# ELVIS.net
KiCad netlist of a schematic drawn in Altium Designer
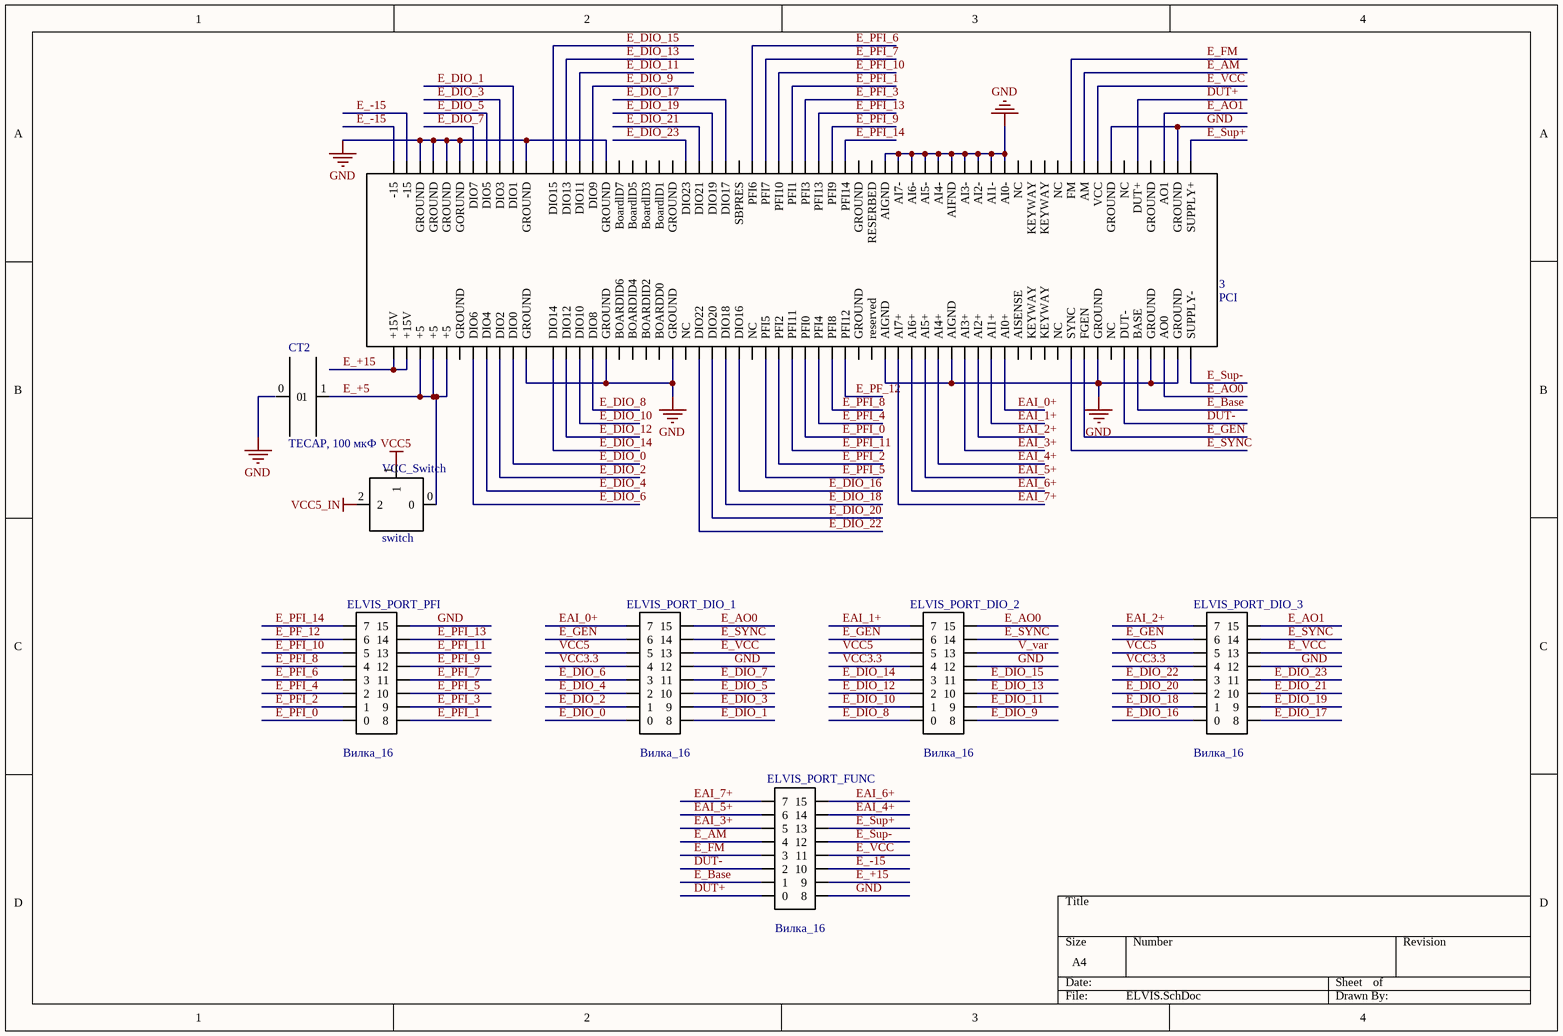
[diagram p0: ELVIS.SchDoc]

(export (version "E")
  (design (tool "Eeschema 10.0.6"))
  (components
    (comp (ref "3") (value "PCI") (footprint "PcbLib1:PCI-120") (libsource (lib "Library") (part "PCI")))
    (comp (ref "CT2")
      (value "TECAP, 100 мкФ")
      (footprint "PcbLib1:tantal cap")
      (libsource (lib "Library") (part "TECAP, 100 мкФ"))
    )
    (comp (ref "ELVIS_PORT_DIO_1")
      (value "Вилка_16")
      (footprint "DS1013-16")
      (description "16_pin")
      (libsource (lib "Library") (part "DS1013-16"))
    )
    (comp (ref "ELVIS_PORT_DIO_2")
      (value "Вилка_16")
      (footprint "DS1013-16")
      (description "16_pin")
      (libsource (lib "Library") (part "DS1013-16"))
    )
    (comp (ref "ELVIS_PORT_DIO_3")
      (value "Вилка_16")
      (footprint "DS1013-16")
      (description "16_pin")
      (libsource (lib "Library") (part "DS1013-16"))
    )
    (comp (ref "ELVIS_PORT_FUNC")
      (value "Вилка_16")
      (footprint "DS1013-16")
      (description "16_pin")
      (libsource (lib "Library") (part "DS1013-16"))
    )
    (comp (ref "ELVIS_PORT_PFI")
      (value "Вилка_16")
      (footprint "DS1013-16")
      (description "16_pin")
      (libsource (lib "Library") (part "DS1013-16"))
    )
    (comp (ref "VCC_Switch")
      (value "switch")
      (footprint "PcbLib1:К(Р)142ЕН5В")
      (libsource (lib "Library") (part "switch"))
    )
  )
  (nets
    (net (code "1") (name "/DUT+") (class "Default")
      (node (ref "3") (pin "63") (pinfunction "DUT+_63") (pintype "passive"))
      (node (ref "ELVIS_PORT_FUNC") (pin "0") (pinfunction "0_0") (pintype "passive"))
    )
    (net (code "2") (name "/DUT-") (class "Default")
      (node (ref "3") (pin "53") (pinfunction "DUT-_53") (pintype "passive"))
      (node (ref "ELVIS_PORT_FUNC") (pin "2") (pinfunction "2_2") (pintype "passive"))
    )
    (net (code "3") (name "/EAI_0+") (class "Default")
      (node (ref "3") (pin "45") (pinfunction "AI0+_45") (pintype "passive"))
      (node (ref "ELVIS_PORT_DIO_1") (pin "7") (pinfunction "7_7") (pintype "passive"))
    )
    (net (code "4") (name "/EAI_1+") (class "Default")
      (node (ref "3") (pin "44") (pinfunction "AI1+_44") (pintype "passive"))
      (node (ref "ELVIS_PORT_DIO_2") (pin "7") (pinfunction "7_7") (pintype "passive"))
    )
    (net (code "5") (name "/EAI_2+") (class "Default")
      (node (ref "3") (pin "43") (pinfunction "AI2+_43") (pintype "passive"))
      (node (ref "ELVIS_PORT_DIO_3") (pin "7") (pinfunction "7_7") (pintype "passive"))
    )
    (net (code "6") (name "/EAI_3+") (class "Default")
      (node (ref "3") (pin "42") (pinfunction "AI3+_42") (pintype "passive"))
      (node (ref "ELVIS_PORT_FUNC") (pin "5") (pinfunction "5_5") (pintype "passive"))
    )
    (net (code "7") (name "/EAI_4+") (class "Default")
      (node (ref "3") (pin "40") (pinfunction "AI4+_40") (pintype "passive"))
      (node (ref "ELVIS_PORT_FUNC") (pin "14") (pinfunction "14_14") (pintype "passive"))
    )
    (net (code "8") (name "/EAI_5+") (class "Default")
      (node (ref "3") (pin "39") (pinfunction "AI5+_39") (pintype "passive"))
      (node (ref "ELVIS_PORT_FUNC") (pin "6") (pinfunction "6_6") (pintype "passive"))
    )
    (net (code "9") (name "/EAI_6+") (class "Default")
      (node (ref "3") (pin "38") (pinfunction "AI6+_38") (pintype "passive"))
      (node (ref "ELVIS_PORT_FUNC") (pin "15") (pinfunction "15_15") (pintype "passive"))
    )
    (net (code "10") (name "/EAI_7+") (class "Default")
      (node (ref "3") (pin "37") (pinfunction "AI7+_37") (pintype "passive"))
      (node (ref "ELVIS_PORT_FUNC") (pin "7") (pinfunction "7_7") (pintype "passive"))
    )
    (net (code "11") (name "/E_+5") (class "Default")
      (node (ref "3") (pin "2") (pinfunction "+5_2") (pintype "passive"))
      (node (ref "3") (pin "3") (pinfunction "+5_3") (pintype "passive"))
      (node (ref "3") (pin "4") (pinfunction "+5_4") (pintype "passive"))
      (node (ref "CT2") (pin "1") (pinfunction "1_1") (pintype "passive"))
      (node (ref "VCC_Switch") (pin "0") (pinfunction "0_0") (pintype "passive"))
    )
    (net (code "12") (name "/E_+15") (class "Default")
      (node (ref "3") (pin "0") (pinfunction "+15V_0") (pintype "passive"))
      (node (ref "3") (pin "1") (pinfunction "+15V_1") (pintype "passive"))
      (node (ref "ELVIS_PORT_FUNC") (pin "9") (pinfunction "9_9") (pintype "passive"))
    )
    (net (code "13") (name "/E_-15") (class "Default")
      (node (ref "3") (pin "116") (pinfunction "-15_116") (pintype "passive"))
      (node (ref "3") (pin "117") (pinfunction "-15_117") (pintype "passive"))
      (node (ref "ELVIS_PORT_FUNC") (pin "10") (pinfunction "10_10") (pintype "passive"))
    )
    (net (code "14") (name "/E_AM") (class "Default")
      (node (ref "3") (pin "67") (pinfunction "AM_67") (pintype "passive"))
      (node (ref "ELVIS_PORT_FUNC") (pin "4") (pinfunction "4_4") (pintype "passive"))
    )
    (net (code "15") (name "/E_AO0") (class "Default")
      (node (ref "3") (pin "56") (pinfunction "AO0_56") (pintype "passive"))
      (node (ref "ELVIS_PORT_DIO_1") (pin "15") (pinfunction "15_15") (pintype "passive"))
      (node (ref "ELVIS_PORT_DIO_2") (pin "15") (pinfunction "15_15") (pintype "passive"))
    )
    (net (code "16") (name "/E_AO1") (class "Default")
      (node (ref "3") (pin "61") (pinfunction "AO1_61") (pintype "passive"))
      (node (ref "ELVIS_PORT_DIO_3") (pin "15") (pinfunction "15_15") (pintype "passive"))
    )
    (net (code "17") (name "/E_Base") (class "Default")
      (node (ref "3") (pin "54") (pinfunction "BASE_54") (pintype "passive"))
      (node (ref "ELVIS_PORT_FUNC") (pin "1") (pinfunction "1_1") (pintype "passive"))
    )
    (net (code "18") (name "/E_DIO_0") (class "Default")
      (node (ref "3") (pin "9") (pinfunction "DIO0_9") (pintype "passive"))
      (node (ref "ELVIS_PORT_DIO_1") (pin "0") (pinfunction "0_0") (pintype "passive"))
    )
    (net (code "19") (name "/E_DIO_1") (class "Default")
      (node (ref "3") (pin "108") (pinfunction "DIO1_108") (pintype "passive"))
      (node (ref "ELVIS_PORT_DIO_1") (pin "8") (pinfunction "8_8") (pintype "passive"))
    )
    (net (code "20") (name "/E_DIO_2") (class "Default")
      (node (ref "3") (pin "8") (pinfunction "DIO2_8") (pintype "passive"))
      (node (ref "ELVIS_PORT_DIO_1") (pin "1") (pinfunction "1_1") (pintype "passive"))
    )
    (net (code "21") (name "/E_DIO_3") (class "Default")
      (node (ref "3") (pin "109") (pinfunction "DIO3_109") (pintype "passive"))
      (node (ref "ELVIS_PORT_DIO_1") (pin "9") (pinfunction "9_9") (pintype "passive"))
    )
    (net (code "22") (name "/E_DIO_4") (class "Default")
      (node (ref "3") (pin "7") (pinfunction "DIO4_7") (pintype "passive"))
      (node (ref "ELVIS_PORT_DIO_1") (pin "2") (pinfunction "2_2") (pintype "passive"))
    )
    (net (code "23") (name "/E_DIO_5") (class "Default")
      (node (ref "3") (pin "110") (pinfunction "DIO5_110") (pintype "passive"))
      (node (ref "ELVIS_PORT_DIO_1") (pin "10") (pinfunction "10_10") (pintype "passive"))
    )
    (net (code "24") (name "/E_DIO_6") (class "Default")
      (node (ref "3") (pin "6") (pinfunction "DIO6_6") (pintype "passive"))
      (node (ref "ELVIS_PORT_DIO_1") (pin "3") (pinfunction "3_3") (pintype "passive"))
    )
    (net (code "25") (name "/E_DIO_7") (class "Default")
      (node (ref "3") (pin "111") (pinfunction "DIO7_111") (pintype "passive"))
      (node (ref "ELVIS_PORT_DIO_1") (pin "11") (pinfunction "11_11") (pintype "passive"))
    )
    (net (code "26") (name "/E_DIO_8") (class "Default")
      (node (ref "3") (pin "14") (pinfunction "DIO8_14") (pintype "passive"))
      (node (ref "ELVIS_PORT_DIO_2") (pin "0") (pinfunction "0_0") (pintype "passive"))
    )
    (net (code "27") (name "/E_DIO_9") (class "Default")
      (node (ref "3") (pin "103") (pinfunction "DIO9_103") (pintype "passive"))
      (node (ref "ELVIS_PORT_DIO_2") (pin "8") (pinfunction "8_8") (pintype "passive"))
    )
    (net (code "28") (name "/E_DIO_10") (class "Default")
      (node (ref "3") (pin "13") (pinfunction "DIO10_13") (pintype "passive"))
      (node (ref "ELVIS_PORT_DIO_2") (pin "1") (pinfunction "1_1") (pintype "passive"))
    )
    (net (code "29") (name "/E_DIO_11") (class "Default")
      (node (ref "3") (pin "104") (pinfunction "DIO11_104") (pintype "passive"))
      (node (ref "ELVIS_PORT_DIO_2") (pin "9") (pinfunction "9_9") (pintype "passive"))
    )
    (net (code "30") (name "/E_DIO_12") (class "Default")
      (node (ref "3") (pin "12") (pinfunction "DIO12_12") (pintype "passive"))
      (node (ref "ELVIS_PORT_DIO_2") (pin "2") (pinfunction "2_2") (pintype "passive"))
    )
    (net (code "31") (name "/E_DIO_13") (class "Default")
      (node (ref "3") (pin "105") (pinfunction "DIO13_105") (pintype "passive"))
      (node (ref "ELVIS_PORT_DIO_2") (pin "10") (pinfunction "10_10") (pintype "passive"))
    )
    (net (code "32") (name "/E_DIO_14") (class "Default")
      (node (ref "3") (pin "11") (pinfunction "DIO14_11") (pintype "passive"))
      (node (ref "ELVIS_PORT_DIO_2") (pin "3") (pinfunction "3_3") (pintype "passive"))
    )
    (net (code "33") (name "/E_DIO_15") (class "Default")
      (node (ref "3") (pin "106") (pinfunction "DIO15_106") (pintype "passive"))
      (node (ref "ELVIS_PORT_DIO_2") (pin "11") (pinfunction "11_11") (pintype "passive"))
    )
    (net (code "34") (name "/E_DIO_16") (class "Default")
      (node (ref "3") (pin "25") (pinfunction "DIO16_25") (pintype "passive"))
      (node (ref "ELVIS_PORT_DIO_3") (pin "0") (pinfunction "0_0") (pintype "passive"))
    )
    (net (code "35") (name "/E_DIO_17") (class "Default")
      (node (ref "3") (pin "93") (pinfunction "DIO17_93") (pintype "passive"))
      (node (ref "ELVIS_PORT_DIO_3") (pin "8") (pinfunction "8_8") (pintype "passive"))
    )
    (net (code "36") (name "/E_DIO_18") (class "Default")
      (node (ref "3") (pin "24") (pinfunction "DIO18_24") (pintype "passive"))
      (node (ref "ELVIS_PORT_DIO_3") (pin "1") (pinfunction "1_1") (pintype "passive"))
    )
    (net (code "37") (name "/E_DIO_19") (class "Default")
      (node (ref "3") (pin "94") (pinfunction "DIO19_94") (pintype "passive"))
      (node (ref "ELVIS_PORT_DIO_3") (pin "9") (pinfunction "9_9") (pintype "passive"))
    )
    (net (code "38") (name "/E_DIO_20") (class "Default")
      (node (ref "3") (pin "23") (pinfunction "DIO20_23") (pintype "passive"))
      (node (ref "ELVIS_PORT_DIO_3") (pin "2") (pinfunction "2_2") (pintype "passive"))
    )
    (net (code "39") (name "/E_DIO_21") (class "Default")
      (node (ref "3") (pin "95") (pinfunction "DIO21_95") (pintype "passive"))
      (node (ref "ELVIS_PORT_DIO_3") (pin "10") (pinfunction "10_10") (pintype "passive"))
    )
    (net (code "40") (name "/E_DIO_22") (class "Default")
      (node (ref "3") (pin "22") (pinfunction "DIO22_22") (pintype "passive"))
      (node (ref "ELVIS_PORT_DIO_3") (pin "3") (pinfunction "3_3") (pintype "passive"))
    )
    (net (code "41") (name "/E_DIO_23") (class "Default")
      (node (ref "3") (pin "96") (pinfunction "DIO23_96") (pintype "passive"))
      (node (ref "ELVIS_PORT_DIO_3") (pin "11") (pinfunction "11_11") (pintype "passive"))
    )
    (net (code "42") (name "/E_FM") (class "Default")
      (node (ref "3") (pin "68") (pinfunction "FM_68") (pintype "passive"))
      (node (ref "ELVIS_PORT_FUNC") (pin "3") (pinfunction "3_3") (pintype "passive"))
    )
    (net (code "43") (name "/E_GEN") (class "Default")
      (node (ref "3") (pin "50") (pinfunction "FGEN_50") (pintype "passive"))
      (node (ref "ELVIS_PORT_DIO_1") (pin "6") (pinfunction "6_6") (pintype "passive"))
      (node (ref "ELVIS_PORT_DIO_2") (pin "6") (pinfunction "6_6") (pintype "passive"))
      (node (ref "ELVIS_PORT_DIO_3") (pin "6") (pinfunction "6_6") (pintype "passive"))
    )
    (net (code "44") (name "/E_PFI_0") (class "Default")
      (node (ref "3") (pin "30") (pinfunction "PFI0_30") (pintype "passive"))
      (node (ref "ELVIS_PORT_PFI") (pin "0") (pinfunction "0_0") (pintype "passive"))
    )
    (net (code "45") (name "/E_PFI_1") (class "Default")
      (node (ref "3") (pin "88") (pinfunction "PFI1_88") (pintype "passive"))
      (node (ref "ELVIS_PORT_PFI") (pin "8") (pinfunction "8_8") (pintype "passive"))
    )
    (net (code "46") (name "/E_PFI_2") (class "Default")
      (node (ref "3") (pin "28") (pinfunction "PFI2_28") (pintype "passive"))
      (node (ref "ELVIS_PORT_PFI") (pin "1") (pinfunction "1_1") (pintype "passive"))
    )
    (net (code "47") (name "/E_PFI_3") (class "Default")
      (node (ref "3") (pin "87") (pinfunction "PFI3_87") (pintype "passive"))
      (node (ref "ELVIS_PORT_PFI") (pin "9") (pinfunction "9_9") (pintype "passive"))
    )
    (net (code "48") (name "/E_PFI_4") (class "Default")
      (node (ref "3") (pin "31") (pinfunction "PFI4_31") (pintype "passive"))
      (node (ref "ELVIS_PORT_PFI") (pin "2") (pinfunction "2_2") (pintype "passive"))
    )
    (net (code "49") (name "/E_PFI_5") (class "Default")
      (node (ref "3") (pin "27") (pinfunction "PFI5_27") (pintype "passive"))
      (node (ref "ELVIS_PORT_PFI") (pin "10") (pinfunction "10_10") (pintype "passive"))
    )
    (net (code "50") (name "/E_PFI_6") (class "Default")
      (node (ref "3") (pin "91") (pinfunction "PFI6_91") (pintype "passive"))
      (node (ref "ELVIS_PORT_PFI") (pin "3") (pinfunction "3_3") (pintype "passive"))
    )
    (net (code "51") (name "/E_PFI_7") (class "Default")
      (node (ref "3") (pin "90") (pinfunction "PFI7_90") (pintype "passive"))
      (node (ref "ELVIS_PORT_PFI") (pin "11") (pinfunction "11_11") (pintype "passive"))
    )
    (net (code "52") (name "/E_PFI_8") (class "Default")
      (node (ref "3") (pin "32") (pinfunction "PFI8_32") (pintype "passive"))
      (node (ref "ELVIS_PORT_PFI") (pin "4") (pinfunction "4_4") (pintype "passive"))
    )
    (net (code "53") (name "/E_PFI_9") (class "Default")
      (node (ref "3") (pin "85") (pinfunction "PFI9_85") (pintype "passive"))
      (node (ref "ELVIS_PORT_PFI") (pin "12") (pinfunction "12_12") (pintype "passive"))
    )
    (net (code "54") (name "/E_PFI_10") (class "Default")
      (node (ref "3") (pin "89") (pinfunction "PFI10_89") (pintype "passive"))
      (node (ref "ELVIS_PORT_PFI") (pin "5") (pinfunction "5_5") (pintype "passive"))
    )
    (net (code "55") (name "/E_PFI_11") (class "Default")
      (node (ref "3") (pin "29") (pinfunction "PFI11_29") (pintype "passive"))
      (node (ref "ELVIS_PORT_PFI") (pin "13") (pinfunction "13_13") (pintype "passive"))
    )
    (net (code "56") (name "/E_PFI_13") (class "Default")
      (node (ref "3") (pin "86") (pinfunction "PFI13_86") (pintype "passive"))
      (node (ref "ELVIS_PORT_PFI") (pin "14") (pinfunction "14_14") (pintype "passive"))
    )
    (net (code "57") (name "/E_PFI_14") (class "Default")
      (node (ref "3") (pin "84") (pinfunction "PFI14_84") (pintype "passive"))
      (node (ref "ELVIS_PORT_PFI") (pin "7") (pinfunction "7_7") (pintype "passive"))
    )
    (net (code "58") (name "/E_PF_12") (class "Default")
      (node (ref "3") (pin "33") (pinfunction "PFI12_33") (pintype "passive"))
      (node (ref "ELVIS_PORT_PFI") (pin "6") (pinfunction "6_6") (pintype "passive"))
    )
    (net (code "59") (name "/E_SYNC") (class "Default")
      (node (ref "3") (pin "49") (pinfunction "SYNC_49") (pintype "passive"))
      (node (ref "ELVIS_PORT_DIO_1") (pin "14") (pinfunction "14_14") (pintype "passive"))
      (node (ref "ELVIS_PORT_DIO_2") (pin "14") (pinfunction "14_14") (pintype "passive"))
      (node (ref "ELVIS_PORT_DIO_3") (pin "14") (pinfunction "14_14") (pintype "passive"))
    )
    (net (code "60") (name "/E_Sup+") (class "Default")
      (node (ref "3") (pin "59") (pinfunction "SUPPLY+_59") (pintype "passive"))
      (node (ref "ELVIS_PORT_FUNC") (pin "13") (pinfunction "13_13") (pintype "passive"))
    )
    (net (code "61") (name "/E_Sup-") (class "Default")
      (node (ref "3") (pin "58") (pinfunction "SUPPLY-_58") (pintype "passive"))
      (node (ref "ELVIS_PORT_FUNC") (pin "12") (pinfunction "12_12") (pintype "passive"))
    )
    (net (code "62") (name "/E_VCC") (class "Default")
      (node (ref "3") (pin "66") (pinfunction "VCC_66") (pintype "passive"))
      (node (ref "ELVIS_PORT_DIO_1") (pin "13") (pinfunction "13_13") (pintype "passive"))
      (node (ref "ELVIS_PORT_DIO_3") (pin "13") (pinfunction "13_13") (pintype "passive"))
      (node (ref "ELVIS_PORT_FUNC") (pin "11") (pinfunction "11_11") (pintype "passive"))
    )
    (net (code "63") (name "/VCC3.3") (class "Default")
      (node (ref "ELVIS_PORT_DIO_1") (pin "4") (pinfunction "4_4") (pintype "passive"))
      (node (ref "ELVIS_PORT_DIO_2") (pin "4") (pinfunction "4_4") (pintype "passive"))
      (node (ref "ELVIS_PORT_DIO_3") (pin "4") (pinfunction "4_4") (pintype "passive"))
    )
    (net (code "64") (name "/V_var") (class "Default")
      (node (ref "ELVIS_PORT_DIO_2") (pin "13") (pinfunction "13_13") (pintype "passive"))
    )
    (net (code "65") (name "GND") (class "Default")
      (node (ref "3") (pin "10") (pinfunction "GROUND_10") (pintype "passive"))
      (node (ref "3") (pin "102") (pinfunction "GROUND_102") (pintype "passive"))
      (node (ref "3") (pin "107") (pinfunction "GROUND_107") (pintype "passive"))
      (node (ref "3") (pin "112") (pinfunction "GORUND_112") (pintype "passive"))
      (node (ref "3") (pin "113") (pinfunction "GROUND_113") (pintype "passive"))
      (node (ref "3") (pin "114") (pinfunction "GROUND_114") (pintype "passive"))
      (node (ref "3") (pin "115") (pinfunction "GROUND_115") (pintype "passive"))
      (node (ref "3") (pin "15") (pinfunction "GROUND_15") (pintype "passive"))
      (node (ref "3") (pin "20") (pinfunction "GROUND_20") (pintype "passive"))
      (node (ref "3") (pin "36") (pinfunction "AIGND_36") (pintype "passive"))
      (node (ref "3") (pin "41") (pinfunction "AIGND_41") (pintype "passive"))
      (node (ref "3") (pin "51") (pinfunction "GROUND_51") (pintype "passive"))
      (node (ref "3") (pin "55") (pinfunction "GROUND_55") (pintype "passive"))
      (node (ref "3") (pin "57") (pinfunction "GROUND_57") (pintype "passive"))
      (node (ref "3") (pin "60") (pinfunction "GROUND_60") (pintype "passive"))
      (node (ref "3") (pin "65") (pinfunction "GROUND_65") (pintype "passive"))
      (node (ref "3") (pin "72") (pinfunction "AI0-_72") (pintype "passive"))
      (node (ref "3") (pin "73") (pinfunction "AI1-_73") (pintype "passive"))
      (node (ref "3") (pin "74") (pinfunction "AI2-_74") (pintype "passive"))
      (node (ref "3") (pin "75") (pinfunction "AI3-_75") (pintype "passive"))
      (node (ref "3") (pin "76") (pinfunction "AIFND_76") (pintype "passive"))
      (node (ref "3") (pin "77") (pinfunction "AI4-_77") (pintype "passive"))
      (node (ref "3") (pin "78") (pinfunction "AI5-_78") (pintype "passive"))
      (node (ref "3") (pin "79") (pinfunction "AI6-_79") (pintype "passive"))
      (node (ref "3") (pin "80") (pinfunction "AI7-_80") (pintype "passive"))
      (node (ref "3") (pin "81") (pinfunction "AIGND_81") (pintype "passive"))
      (node (ref "ELVIS_PORT_DIO_1") (pin "12") (pinfunction "12_12") (pintype "passive"))
      (node (ref "ELVIS_PORT_DIO_2") (pin "12") (pinfunction "12_12") (pintype "passive"))
      (node (ref "ELVIS_PORT_DIO_3") (pin "12") (pinfunction "12_12") (pintype "passive"))
      (node (ref "ELVIS_PORT_FUNC") (pin "8") (pinfunction "8_8") (pintype "passive"))
      (node (ref "ELVIS_PORT_PFI") (pin "15") (pinfunction "15_15") (pintype "passive"))
    )
    (net (code "66") (name "VCC5") (class "Default")
      (node (ref "ELVIS_PORT_DIO_1") (pin "5") (pinfunction "5_5") (pintype "passive"))
      (node (ref "ELVIS_PORT_DIO_2") (pin "5") (pinfunction "5_5") (pintype "passive"))
      (node (ref "ELVIS_PORT_DIO_3") (pin "5") (pinfunction "5_5") (pintype "passive"))
      (node (ref "VCC_Switch") (pin "1") (pinfunction "1_1") (pintype "passive"))
    )
    (net (code "67") (name "VCC5_IN") (class "Default")
      (node (ref "VCC_Switch") (pin "2") (pinfunction "2_2") (pintype "passive"))
    )
    (net (code "68") (name "unconnected-(3-AISENSE-Pad46)") (class "Default")
      (node (ref "3") (pin "46") (pinfunction "AISENSE_46") (pintype "passive"))
    )
    (net (code "69") (name "unconnected-(3-BOARDD0-Pad19)") (class "Default")
      (node (ref "3") (pin "19") (pinfunction "BOARDD0_19") (pintype "passive"))
    )
    (net (code "70") (name "unconnected-(3-BOARDID2-Pad18)") (class "Default")
      (node (ref "3") (pin "18") (pinfunction "BOARDID2_18") (pintype "passive"))
    )
    (net (code "71") (name "unconnected-(3-BOARDID4-Pad17)") (class "Default")
      (node (ref "3") (pin "17") (pinfunction "BOARDID4_17") (pintype "passive"))
    )
    (net (code "72") (name "unconnected-(3-BOARDID6-Pad16)") (class "Default")
      (node (ref "3") (pin "16") (pinfunction "BOARDID6_16") (pintype "passive"))
    )
    (net (code "73") (name "unconnected-(3-BoardlD1-Pad98)") (class "Default")
      (node (ref "3") (pin "98") (pinfunction "BoardlD1_98") (pintype "passive"))
    )
    (net (code "74") (name "unconnected-(3-BoardlD3-Pad99)") (class "Default")
      (node (ref "3") (pin "99") (pinfunction "BoardlD3_99") (pintype "passive"))
    )
    (net (code "75") (name "unconnected-(3-BoardlD5-Pad100)") (class "Default")
      (node (ref "3") (pin "100") (pinfunction "BoardlD5_100") (pintype "passive"))
    )
    (net (code "76") (name "unconnected-(3-BoardlD7-Pad101)") (class "Default")
      (node (ref "3") (pin "101") (pinfunction "BoardlD7_101") (pintype "passive"))
    )
    (net (code "77") (name "unconnected-(3-GROUND-Pad5)") (class "Default")
      (node (ref "3") (pin "5") (pinfunction "GROUND_5") (pintype "passive"))
    )
    (net (code "78") (name "unconnected-(3-GROUND-Pad34)") (class "Default")
      (node (ref "3") (pin "34") (pinfunction "GROUND_34") (pintype "passive"))
    )
    (net (code "79") (name "unconnected-(3-GROUND-Pad62)") (class "Default")
      (node (ref "3") (pin "62") (pinfunction "GROUND_62") (pintype "passive"))
    )
    (net (code "80") (name "unconnected-(3-GROUND-Pad83)") (class "Default")
      (node (ref "3") (pin "83") (pinfunction "GROUND_83") (pintype "passive"))
    )
    (net (code "81") (name "unconnected-(3-GROUND-Pad97)") (class "Default")
      (node (ref "3") (pin "97") (pinfunction "GROUND_97") (pintype "passive"))
    )
    (net (code "82") (name "unconnected-(3-KEYWAY-Pad47)") (class "Default")
      (node (ref "3") (pin "47") (pinfunction "KEYWAY_47") (pintype "passive"))
    )
    (net (code "83") (name "unconnected-(3-KEYWAY-Pad70)") (class "Default")
      (node (ref "3") (pin "70") (pinfunction "KEYWAY_70") (pintype "passive"))
    )
    (net (code "84") (name "unconnected-(3-KEYWAY-Pad118)") (class "Default")
      (node (ref "3") (pin "118") (pinfunction "KEYWAY_118") (pintype "passive"))
    )
    (net (code "85") (name "unconnected-(3-KEYWAY-Pad119)") (class "Default")
      (node (ref "3") (pin "119") (pinfunction "KEYWAY_119") (pintype "passive"))
    )
    (net (code "86") (name "unconnected-(3-NC-Pad21)") (class "Default")
      (node (ref "3") (pin "21") (pinfunction "NC_21") (pintype "passive"))
    )
    (net (code "87") (name "unconnected-(3-NC-Pad26)") (class "Default")
      (node (ref "3") (pin "26") (pinfunction "NC_26") (pintype "passive"))
    )
    (net (code "88") (name "unconnected-(3-NC-Pad48)") (class "Default")
      (node (ref "3") (pin "48") (pinfunction "NC_48") (pintype "passive"))
    )
    (net (code "89") (name "unconnected-(3-NC-Pad52)") (class "Default")
      (node (ref "3") (pin "52") (pinfunction "NC_52") (pintype "passive"))
    )
    (net (code "90") (name "unconnected-(3-NC-Pad64)") (class "Default")
      (node (ref "3") (pin "64") (pinfunction "NC_64") (pintype "passive"))
    )
    (net (code "91") (name "unconnected-(3-NC-Pad69)") (class "Default")
      (node (ref "3") (pin "69") (pinfunction "NC_69") (pintype "passive"))
    )
    (net (code "92") (name "unconnected-(3-NC-Pad71)") (class "Default")
      (node (ref "3") (pin "71") (pinfunction "NC_71") (pintype "passive"))
    )
    (net (code "93") (name "unconnected-(3-RESERBED-Pad82)") (class "Default")
      (node (ref "3") (pin "82") (pinfunction "RESERBED_82") (pintype "passive"))
    )
    (net (code "94") (name "unconnected-(3-SBPRES-Pad92)") (class "Default")
      (node (ref "3") (pin "92") (pinfunction "SBPRES_92") (pintype "passive"))
    )
    (net (code "95") (name "unconnected-(3-reserved-Pad35)") (class "Default")
      (node (ref "3") (pin "35") (pinfunction "reserved_35") (pintype "passive"))
    )
    (net (code "96") (name "unconnected-(CT2-Pad0)") (class "Default")
      (node (ref "CT2") (pin "0") (pinfunction "0_0") (pintype "passive"))
    )
  )
)
